# BOTTOM_BOARD.net
KiCad netlist of a schematic drawn in Altium Designer
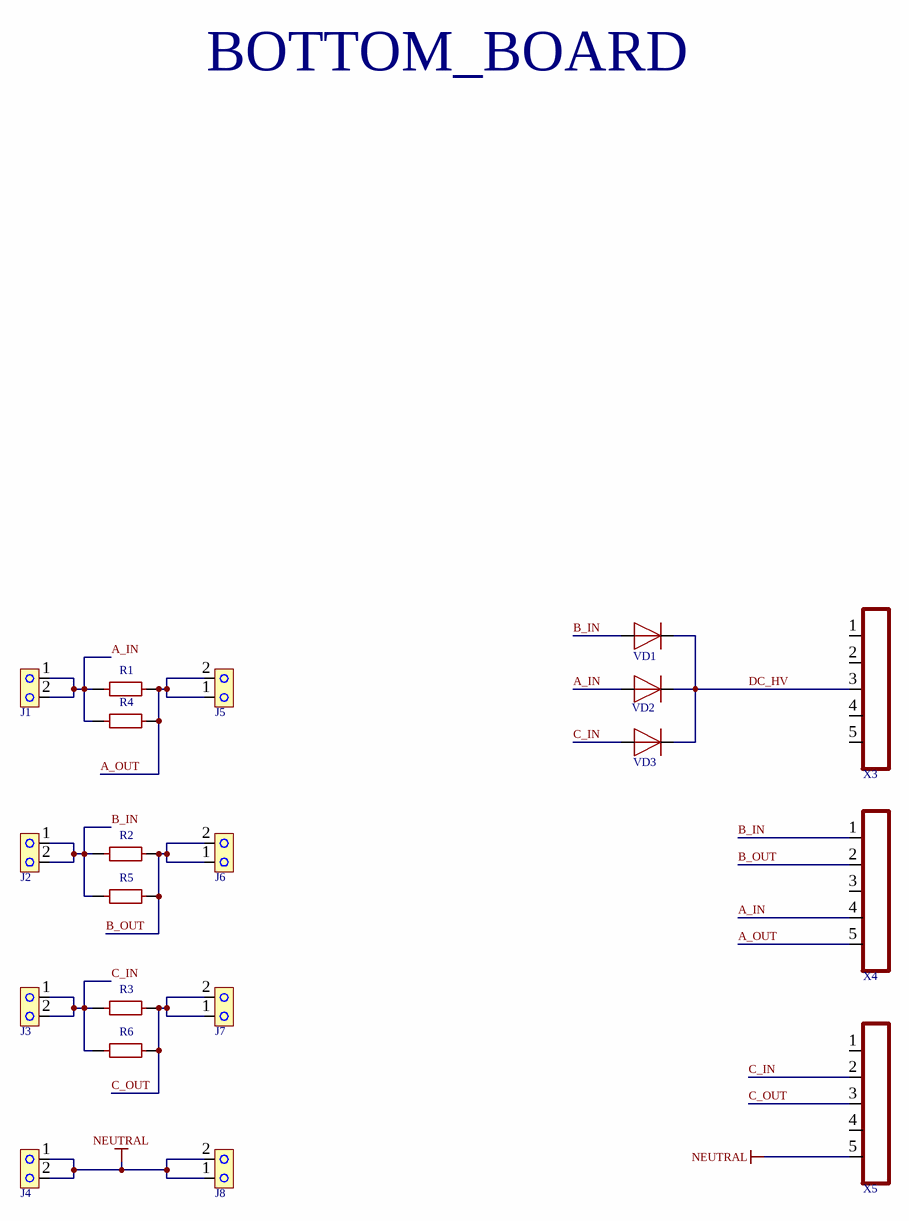
[diagram p0: BOTTOM_BOARD.SchDoc]

(export (version "E")
  (design (tool "Eeschema 10.0.6"))
  (components
    (comp (ref "J1")
      (value "TL-800")
      (footprint "Conn_Tianli_T-800")
      (libsource (lib "") (part "Connector_Tianli_T-800_1"))
    )
    (comp (ref "J2")
      (value "TL-800")
      (footprint "Conn_Tianli_T-800")
      (libsource (lib "") (part "Connector_Tianli_T-800_1"))
    )
    (comp (ref "J3")
      (value "TL-800")
      (footprint "Conn_Tianli_T-800")
      (libsource (lib "") (part "Connector_Tianli_T-800_1"))
    )
    (comp (ref "J4")
      (value "TL-800")
      (footprint "Conn_Tianli_T-800")
      (libsource (lib "") (part "Connector_Tianli_T-800_1"))
    )
    (comp (ref "J5")
      (value "TL-800")
      (footprint "Conn_Tianli_T-800")
      (libsource (lib "T800") (part "Connector_Tianli_T-800"))
    )
    (comp (ref "J6")
      (value "TL-800")
      (footprint "Conn_Tianli_T-800")
      (libsource (lib "T800") (part "Connector_Tianli_T-800"))
    )
    (comp (ref "J7")
      (value "TL-800")
      (footprint "Conn_Tianli_T-800")
      (libsource (lib "T800") (part "Connector_Tianli_T-800"))
    )
    (comp (ref "J8")
      (value "TL-800")
      (footprint "Conn_Tianli_T-800")
      (libsource (lib "T800") (part "Connector_Tianli_T-800"))
    )
    (comp (ref "R1")
      (value "RES-CONST")
      (footprint "RES-3921")
      (libsource (lib "PASSIVE_COMPONENTS") (part "RES-CONST"))
    )
    (comp (ref "R2")
      (value "RES-CONST")
      (footprint "RES-3921")
      (libsource (lib "PASSIVE_COMPONENTS") (part "RES-CONST"))
    )
    (comp (ref "R3")
      (value "RES-CONST")
      (footprint "RES-3921")
      (libsource (lib "PASSIVE_COMPONENTS") (part "RES-CONST"))
    )
    (comp (ref "R4")
      (value "RES-CONST")
      (footprint "RES-3921")
      (libsource (lib "PASSIVE_COMPONENTS") (part "RES-CONST"))
    )
    (comp (ref "R5")
      (value "RES-CONST")
      (footprint "RES-3921")
      (libsource (lib "PASSIVE_COMPONENTS") (part "RES-CONST"))
    )
    (comp (ref "R6")
      (value "RES-CONST")
      (footprint "RES-3921")
      (libsource (lib "PASSIVE_COMPONENTS") (part "RES-CONST"))
    )
    (comp (ref "VD1")
      (value "DIODE")
      (footprint "DO-214BA")
      (libsource (lib "PASSIVE_COMPONENTS") (part "DIODE"))
    )
    (comp (ref "VD2")
      (value "DIODE")
      (footprint "DO-214BA")
      (libsource (lib "PASSIVE_COMPONENTS") (part "DIODE"))
    )
    (comp (ref "VD3")
      (value "DIODE")
      (footprint "DO-214BA")
      (libsource (lib "PASSIVE_COMPONENTS") (part "DIODE"))
    )
    (comp (ref "X3")
      (value "CONN-5-PIN")
      (footprint "CONN-PLS-5-2.54mm")
      (libsource (lib "CONNECTORS") (part "CONN-5-PIN"))
    )
    (comp (ref "X4")
      (value "CONN-5-PIN")
      (footprint "CONN-PLS-5-2.54mm")
      (libsource (lib "CONNECTORS") (part "CONN-5-PIN"))
    )
    (comp (ref "X5")
      (value "CONN-5-PIN")
      (footprint "CONN-PLS-5-2.54mm")
      (libsource (lib "CONNECTORS") (part "CONN-5-PIN"))
    )
  )
  (nets
    (net (code "1") (name "/A_IN") (class "Default")
      (node (ref "J1") (pin "1") (pinfunction "17_1") (pintype "passive"))
      (node (ref "J1") (pin "2") (pinfunction "2_2") (pintype "passive"))
      (node (ref "R1") (pin "1") (pinfunction "1_1") (pintype "passive"))
      (node (ref "R4") (pin "1") (pinfunction "1_1") (pintype "passive"))
      (node (ref "VD2") (pin "2") (pinfunction "A_2") (pintype "passive"))
      (node (ref "X4") (pin "4") (pinfunction "4_4") (pintype "passive"))
    )
    (net (code "2") (name "/A_OUT") (class "Default")
      (node (ref "J5") (pin "1") (pinfunction "17_1") (pintype "passive"))
      (node (ref "J5") (pin "2") (pinfunction "2_2") (pintype "passive"))
      (node (ref "R1") (pin "2") (pinfunction "2_2") (pintype "passive"))
      (node (ref "R4") (pin "2") (pinfunction "2_2") (pintype "passive"))
      (node (ref "X4") (pin "5") (pinfunction "5_5") (pintype "passive"))
    )
    (net (code "3") (name "/B_IN") (class "Default")
      (node (ref "J2") (pin "1") (pinfunction "17_1") (pintype "passive"))
      (node (ref "J2") (pin "2") (pinfunction "2_2") (pintype "passive"))
      (node (ref "R2") (pin "1") (pinfunction "1_1") (pintype "passive"))
      (node (ref "R5") (pin "1") (pinfunction "1_1") (pintype "passive"))
      (node (ref "VD1") (pin "2") (pinfunction "A_2") (pintype "passive"))
      (node (ref "X4") (pin "1") (pinfunction "1_1") (pintype "passive"))
    )
    (net (code "4") (name "/B_OUT") (class "Default")
      (node (ref "J6") (pin "1") (pinfunction "17_1") (pintype "passive"))
      (node (ref "J6") (pin "2") (pinfunction "2_2") (pintype "passive"))
      (node (ref "R2") (pin "2") (pinfunction "2_2") (pintype "passive"))
      (node (ref "R5") (pin "2") (pinfunction "2_2") (pintype "passive"))
      (node (ref "X4") (pin "2") (pinfunction "2_2") (pintype "passive"))
    )
    (net (code "5") (name "/C_IN") (class "Default")
      (node (ref "J3") (pin "1") (pinfunction "17_1") (pintype "passive"))
      (node (ref "J3") (pin "2") (pinfunction "2_2") (pintype "passive"))
      (node (ref "R3") (pin "1") (pinfunction "1_1") (pintype "passive"))
      (node (ref "R6") (pin "1") (pinfunction "1_1") (pintype "passive"))
      (node (ref "VD3") (pin "2") (pinfunction "A_2") (pintype "passive"))
      (node (ref "X5") (pin "2") (pinfunction "2_2") (pintype "passive"))
    )
    (net (code "6") (name "/C_OUT") (class "Default")
      (node (ref "J7") (pin "1") (pinfunction "17_1") (pintype "passive"))
      (node (ref "J7") (pin "2") (pinfunction "2_2") (pintype "passive"))
      (node (ref "R3") (pin "2") (pinfunction "2_2") (pintype "passive"))
      (node (ref "R6") (pin "2") (pinfunction "2_2") (pintype "passive"))
      (node (ref "X5") (pin "3") (pinfunction "3_3") (pintype "passive"))
    )
    (net (code "7") (name "/DC_HV") (class "Default")
      (node (ref "VD1") (pin "1") (pinfunction "C_1") (pintype "passive"))
      (node (ref "VD2") (pin "1") (pinfunction "C_1") (pintype "passive"))
      (node (ref "VD3") (pin "1") (pinfunction "C_1") (pintype "passive"))
      (node (ref "X3") (pin "3") (pinfunction "3_3") (pintype "passive"))
    )
    (net (code "8") (name "NEUTRAL") (class "Default")
      (node (ref "J4") (pin "1") (pinfunction "17_1") (pintype "passive"))
      (node (ref "J4") (pin "2") (pinfunction "2_2") (pintype "passive"))
      (node (ref "J8") (pin "1") (pinfunction "17_1") (pintype "passive"))
      (node (ref "J8") (pin "2") (pinfunction "2_2") (pintype "passive"))
      (node (ref "X5") (pin "5") (pinfunction "5_5") (pintype "passive"))
    )
    (net (code "9") (name "unconnected-(X3-Pad1)") (class "Default")
      (node (ref "X3") (pin "1") (pinfunction "1_1") (pintype "passive"))
    )
    (net (code "10") (name "unconnected-(X3-Pad2)") (class "Default")
      (node (ref "X3") (pin "2") (pinfunction "2_2") (pintype "passive"))
    )
    (net (code "11") (name "unconnected-(X3-Pad4)") (class "Default")
      (node (ref "X3") (pin "4") (pinfunction "4_4") (pintype "passive"))
    )
    (net (code "12") (name "unconnected-(X3-Pad5)") (class "Default")
      (node (ref "X3") (pin "5") (pinfunction "5_5") (pintype "passive"))
    )
    (net (code "13") (name "unconnected-(X4-Pad3)") (class "Default")
      (node (ref "X4") (pin "3") (pinfunction "3_3") (pintype "passive"))
    )
    (net (code "14") (name "unconnected-(X5-Pad1)") (class "Default")
      (node (ref "X5") (pin "1") (pinfunction "1_1") (pintype "passive"))
    )
    (net (code "15") (name "unconnected-(X5-Pad4)") (class "Default")
      (node (ref "X5") (pin "4") (pinfunction "4_4") (pintype "passive"))
    )
  )
)
